# 07_DDR3.net
KiCad netlist of a schematic drawn in Altium Designer
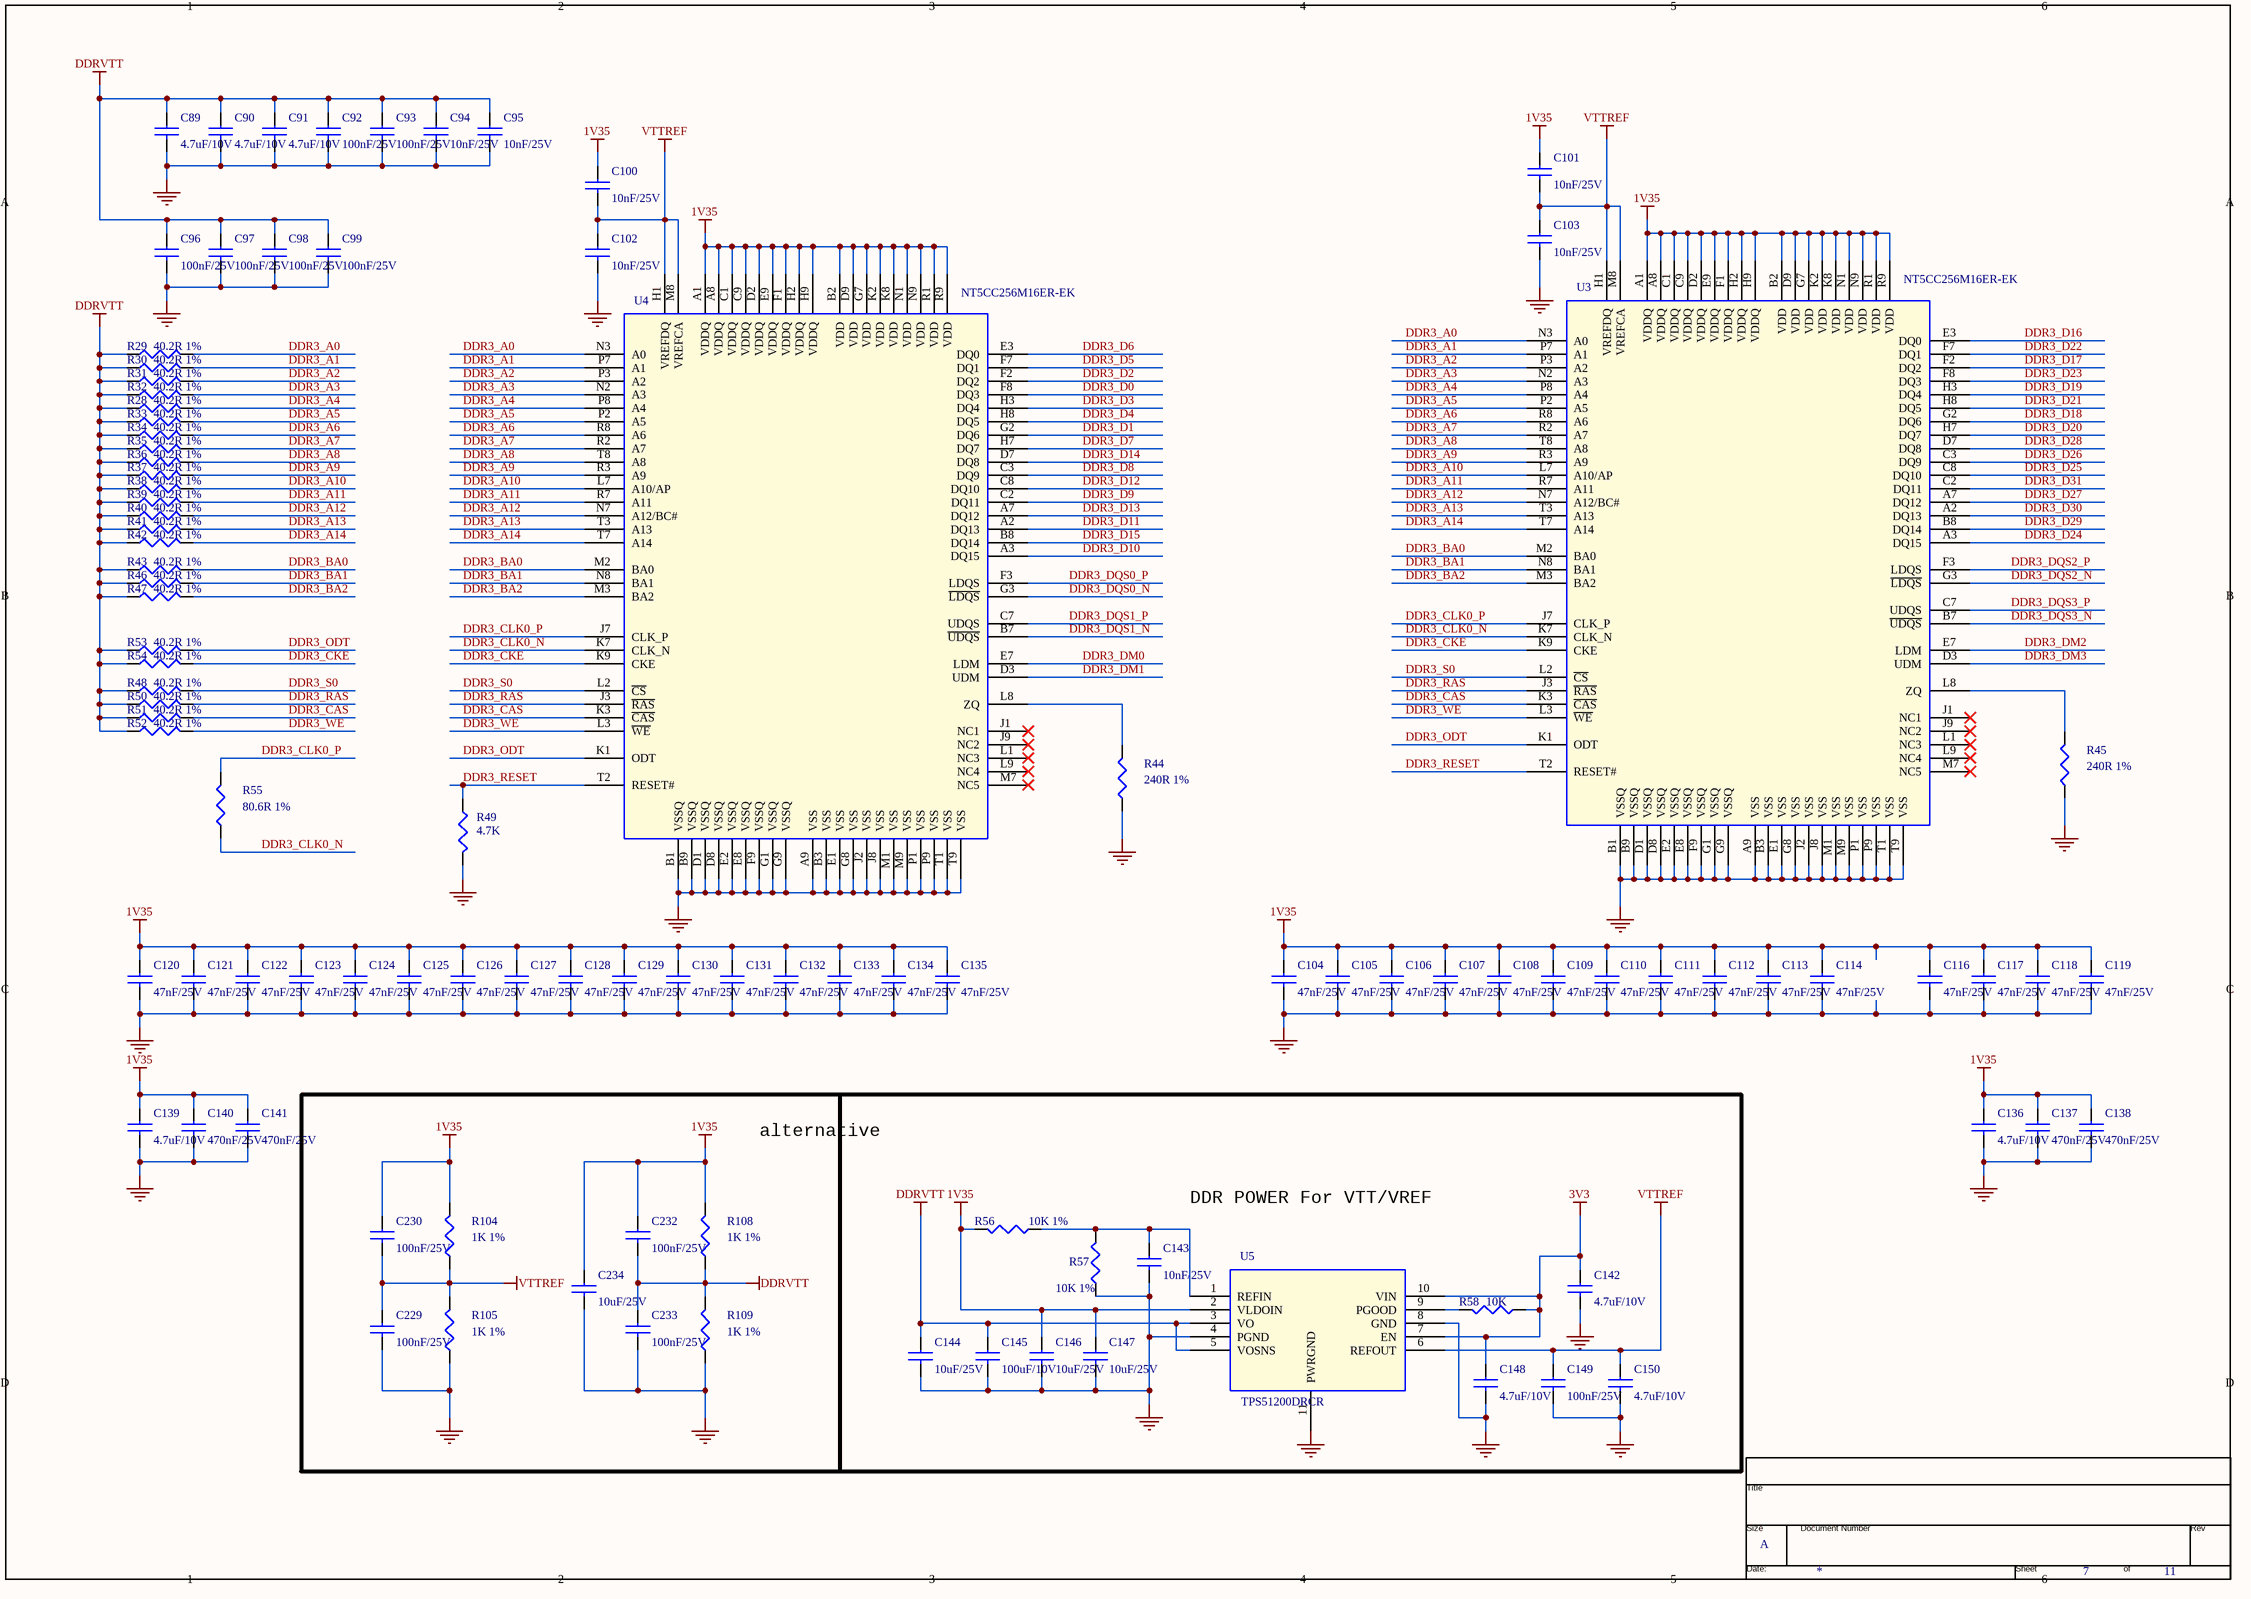
[diagram p0: 07_DDR3.SchDoc]

(export (version "E")
  (design (tool "Eeschema 10.0.6"))
  (components
    (comp (ref "C89") (value "4.7uF/10V") (footprint "C0402") (libsource (lib "*") (part "CAP NP_Dup1")))
    (comp (ref "C90") (value "4.7uF/10V") (footprint "C0402") (libsource (lib "*") (part "CAP NP_Dup1")))
    (comp (ref "C91") (value "4.7uF/10V") (footprint "C0402") (libsource (lib "*") (part "CAP NP_Dup1")))
    (comp (ref "C92") (value "100nF/25V") (footprint "C0402") (libsource (lib "*") (part "CAP NP_Dup1")))
    (comp (ref "C93") (value "100nF/25V") (footprint "C0402") (libsource (lib "*") (part "CAP NP_Dup1")))
    (comp (ref "C94") (value "10nF/25V") (footprint "C0402") (libsource (lib "*") (part "CAP NP_Dup1")))
    (comp (ref "C95") (value "10nF/25V") (footprint "C0402") (libsource (lib "*") (part "CAP NP_Dup1")))
    (comp (ref "C96") (value "100nF/25V") (footprint "C0402") (libsource (lib "*") (part "CAP NP_Dup1")))
    (comp (ref "C97") (value "100nF/25V") (footprint "C0402") (libsource (lib "*") (part "CAP NP_Dup1")))
    (comp (ref "C98") (value "100nF/25V") (footprint "C0402") (libsource (lib "*") (part "CAP NP_Dup1")))
    (comp (ref "C99") (value "100nF/25V") (footprint "C0402") (libsource (lib "*") (part "CAP NP_Dup1")))
    (comp (ref "C100") (value "10nF/25V") (footprint "C0402") (libsource (lib "*") (part "CAP NP_Dup1")))
    (comp (ref "C101") (value "10nF/25V") (footprint "C0402") (libsource (lib "*") (part "CAP NP_Dup1")))
    (comp (ref "C102") (value "10nF/25V") (footprint "C0402") (libsource (lib "*") (part "CAP NP_Dup1")))
    (comp (ref "C103") (value "10nF/25V") (footprint "C0402") (libsource (lib "*") (part "CAP NP_Dup1")))
    (comp (ref "C104") (value "47nF/25V") (footprint "C0402") (libsource (lib "*") (part "CAP NP_Dup1")))
    (comp (ref "C105") (value "47nF/25V") (footprint "C0402") (libsource (lib "*") (part "CAP NP_Dup1")))
    (comp (ref "C106") (value "47nF/25V") (footprint "C0402") (libsource (lib "*") (part "CAP NP_Dup1")))
    (comp (ref "C107") (value "47nF/25V") (footprint "C0402") (libsource (lib "*") (part "CAP NP_Dup1")))
    (comp (ref "C108") (value "47nF/25V") (footprint "C0402") (libsource (lib "*") (part "CAP NP_Dup1")))
    (comp (ref "C109") (value "47nF/25V") (footprint "C0402") (libsource (lib "*") (part "CAP NP_Dup1")))
    (comp (ref "C110") (value "47nF/25V") (footprint "C0402") (libsource (lib "*") (part "CAP NP_Dup1")))
    (comp (ref "C111") (value "47nF/25V") (footprint "C0402") (libsource (lib "*") (part "CAP NP_Dup1")))
    (comp (ref "C112") (value "47nF/25V") (footprint "C0402") (libsource (lib "*") (part "CAP NP_Dup1")))
    (comp (ref "C113") (value "47nF/25V") (footprint "C0402") (libsource (lib "*") (part "CAP NP_Dup1")))
    (comp (ref "C114") (value "47nF/25V") (footprint "C0402") (libsource (lib "*") (part "CAP NP_Dup1")))
    (comp (ref "C116") (value "47nF/25V") (footprint "C0402") (libsource (lib "*") (part "CAP NP_Dup1")))
    (comp (ref "C117") (value "47nF/25V") (footprint "C0402") (libsource (lib "*") (part "CAP NP_Dup1")))
    (comp (ref "C118") (value "47nF/25V") (footprint "C0402") (libsource (lib "*") (part "CAP NP_Dup1")))
    (comp (ref "C119") (value "47nF/25V") (footprint "C0402") (libsource (lib "*") (part "CAP NP_Dup1")))
    (comp (ref "C120") (value "47nF/25V") (footprint "C0402") (libsource (lib "*") (part "CAP NP_Dup1")))
    (comp (ref "C121") (value "47nF/25V") (footprint "C0402") (libsource (lib "*") (part "CAP NP_Dup1")))
    (comp (ref "C122") (value "47nF/25V") (footprint "C0402") (libsource (lib "*") (part "CAP NP_Dup1")))
    (comp (ref "C123") (value "47nF/25V") (footprint "C0402") (libsource (lib "*") (part "CAP NP_Dup1")))
    (comp (ref "C124") (value "47nF/25V") (footprint "C0402") (libsource (lib "*") (part "CAP NP_Dup1")))
    (comp (ref "C125") (value "47nF/25V") (footprint "C0402") (libsource (lib "*") (part "CAP NP_Dup1")))
    (comp (ref "C126") (value "47nF/25V") (footprint "C0402") (libsource (lib "*") (part "CAP NP_Dup1")))
    (comp (ref "C127") (value "47nF/25V") (footprint "C0402") (libsource (lib "*") (part "CAP NP_Dup1")))
    (comp (ref "C128") (value "47nF/25V") (footprint "C0402") (libsource (lib "*") (part "CAP NP_Dup1")))
    (comp (ref "C129") (value "47nF/25V") (footprint "C0402") (libsource (lib "*") (part "CAP NP_Dup1")))
    (comp (ref "C130") (value "47nF/25V") (footprint "C0402") (libsource (lib "*") (part "CAP NP_Dup1")))
    (comp (ref "C131") (value "47nF/25V") (footprint "C0402") (libsource (lib "*") (part "CAP NP_Dup1")))
    (comp (ref "C132") (value "47nF/25V") (footprint "C0402") (libsource (lib "*") (part "CAP NP_Dup1")))
    (comp (ref "C133") (value "47nF/25V") (footprint "C0402") (libsource (lib "*") (part "CAP NP_Dup1")))
    (comp (ref "C134") (value "47nF/25V") (footprint "C0402") (libsource (lib "*") (part "CAP NP_Dup1")))
    (comp (ref "C135") (value "47nF/25V") (footprint "C0402") (libsource (lib "*") (part "CAP NP_Dup1")))
    (comp (ref "C136") (value "4.7uF/10V") (footprint "C0402") (libsource (lib "*") (part "CAP NP_Dup1")))
    (comp (ref "C137") (value "470nF/25V") (footprint "C0402") (libsource (lib "*") (part "CAP NP_Dup1")))
    (comp (ref "C138") (value "470nF/25V") (footprint "C0402") (libsource (lib "*") (part "CAP NP_Dup1")))
    (comp (ref "C139") (value "4.7uF/10V") (footprint "C0402") (libsource (lib "*") (part "CAP NP_Dup1")))
    (comp (ref "C140") (value "470nF/25V") (footprint "C0402") (libsource (lib "*") (part "CAP NP_Dup1")))
    (comp (ref "C141") (value "470nF/25V") (footprint "C0402") (libsource (lib "*") (part "CAP NP_Dup1")))
    (comp (ref "C142") (value "4.7uF/10V") (footprint "C0402") (libsource (lib "*") (part "CAP NP_Dup1")))
    (comp (ref "C143") (value "10nF/25V") (footprint "C0402") (libsource (lib "*") (part "CAP NP_Dup1")))
    (comp (ref "C144") (value "10uF/25V") (footprint "C0603") (libsource (lib "*") (part "CAP NP_Dup1")))
    (comp (ref "C145") (value "100uF/10V") (footprint "1206C-N") (libsource (lib "*") (part "CAP NP_Dup1")))
    (comp (ref "C146") (value "10uF/25V") (footprint "C0603") (libsource (lib "*") (part "CAP NP_Dup1")))
    (comp (ref "C147") (value "10uF/25V") (footprint "C0603") (libsource (lib "*") (part "CAP NP_Dup1")))
    (comp (ref "C148") (value "4.7uF/10V") (footprint "C0402") (libsource (lib "*") (part "CAP NP_Dup1")))
    (comp (ref "C149") (value "100nF/25V") (footprint "C0402") (libsource (lib "*") (part "CAP NP_Dup1")))
    (comp (ref "C150") (value "4.7uF/10V") (footprint "C0402") (libsource (lib "*") (part "CAP NP_Dup1")))
    (comp (ref "C229") (value "100nF/25V") (footprint "C0402") (libsource (lib "*") (part "CAP NP_Dup1")))
    (comp (ref "C230") (value "100nF/25V") (footprint "C0402") (libsource (lib "*") (part "CAP NP_Dup1")))
    (comp (ref "C232") (value "100nF/25V") (footprint "C0402") (libsource (lib "*") (part "CAP NP_Dup1")))
    (comp (ref "C233") (value "100nF/25V") (footprint "C0402") (libsource (lib "*") (part "CAP NP_Dup1")))
    (comp (ref "C234") (value "10uF/25V") (footprint "C0603") (libsource (lib "*") (part "CAP NP_Dup1")))
    (comp (ref "R28") (value "40.2R 1%") (footprint "R0402") (libsource (lib "*") (part "RESISTOR_Dup1")))
    (comp (ref "R29") (value "40.2R 1%") (footprint "R0402") (libsource (lib "*") (part "RESISTOR_Dup1")))
    (comp (ref "R30") (value "40.2R 1%") (footprint "R0402") (libsource (lib "*") (part "RESISTOR_Dup1")))
    (comp (ref "R31") (value "40.2R 1%") (footprint "R0402") (libsource (lib "*") (part "RESISTOR_Dup1")))
    (comp (ref "R32") (value "40.2R 1%") (footprint "R0402") (libsource (lib "*") (part "RESISTOR_Dup1")))
    (comp (ref "R33") (value "40.2R 1%") (footprint "R0402") (libsource (lib "*") (part "RESISTOR_Dup1")))
    (comp (ref "R34") (value "40.2R 1%") (footprint "R0402") (libsource (lib "*") (part "RESISTOR_Dup1")))
    (comp (ref "R35") (value "40.2R 1%") (footprint "R0402") (libsource (lib "*") (part "RESISTOR_Dup1")))
    (comp (ref "R36") (value "40.2R 1%") (footprint "R0402") (libsource (lib "*") (part "RESISTOR_Dup1")))
    (comp (ref "R37") (value "40.2R 1%") (footprint "R0402") (libsource (lib "*") (part "RESISTOR_Dup1")))
    (comp (ref "R38") (value "40.2R 1%") (footprint "R0402") (libsource (lib "*") (part "RESISTOR_Dup1")))
    (comp (ref "R39") (value "40.2R 1%") (footprint "R0402") (libsource (lib "*") (part "RESISTOR_Dup1")))
    (comp (ref "R40") (value "40.2R 1%") (footprint "R0402") (libsource (lib "*") (part "RESISTOR_Dup1")))
    (comp (ref "R41") (value "40.2R 1%") (footprint "R0402") (libsource (lib "*") (part "RESISTOR_Dup1")))
    (comp (ref "R42") (value "40.2R 1%") (footprint "R0402") (libsource (lib "*") (part "RESISTOR_Dup1")))
    (comp (ref "R43") (value "40.2R 1%") (footprint "R0402") (libsource (lib "*") (part "RESISTOR_Dup1")))
    (comp (ref "R44") (value "240R 1%") (footprint "R0402") (libsource (lib "*") (part "RESISTOR_Dup1")))
    (comp (ref "R45") (value "240R 1%") (footprint "R0402") (libsource (lib "*") (part "RESISTOR_Dup1")))
    (comp (ref "R46") (value "40.2R 1%") (footprint "R0402") (libsource (lib "*") (part "RESISTOR_Dup1")))
    (comp (ref "R47") (value "40.2R 1%") (footprint "R0402") (libsource (lib "*") (part "RESISTOR_Dup1")))
    (comp (ref "R48") (value "40.2R 1%") (footprint "R0402") (libsource (lib "*") (part "RESISTOR_Dup1")))
    (comp (ref "R49") (value "4.7K") (footprint "R0402") (libsource (lib "*") (part "RESISTOR_Dup1")))
    (comp (ref "R50") (value "40.2R 1%") (footprint "R0402") (libsource (lib "*") (part "RESISTOR_Dup1")))
    (comp (ref "R51") (value "40.2R 1%") (footprint "R0402") (libsource (lib "*") (part "RESISTOR_Dup1")))
    (comp (ref "R52") (value "40.2R 1%") (footprint "R0402") (libsource (lib "*") (part "RESISTOR_Dup1")))
    (comp (ref "R53") (value "40.2R 1%") (footprint "R0402") (libsource (lib "*") (part "RESISTOR_Dup1")))
    (comp (ref "R54") (value "40.2R 1%") (footprint "R0402") (libsource (lib "*") (part "RESISTOR_Dup1")))
    (comp (ref "R55") (value "80.6R 1%") (footprint "R0402") (libsource (lib "*") (part "RESISTOR_Dup1")))
    (comp (ref "R56") (value "10K 1%") (footprint "R0402") (libsource (lib "*") (part "RESISTOR_Dup1")))
    (comp (ref "R57") (value "10K 1%") (footprint "R0402") (libsource (lib "*") (part "RESISTOR_Dup1")))
    (comp (ref "R58") (value "10K") (footprint "R0402") (libsource (lib "*") (part "RESISTOR_Dup1")))
    (comp (ref "R104") (value "1K 1%") (footprint "R0402") (libsource (lib "*") (part "RESISTOR_Dup1")))
    (comp (ref "R105") (value "1K 1%") (footprint "R0402") (libsource (lib "*") (part "RESISTOR_Dup1")))
    (comp (ref "R108")
      (value "1K 1%")
      (footprint "R0603")
      (description "0603")
      (libsource (lib "*") (part "RESISTOR_Dup1"))
    )
    (comp (ref "R109")
      (value "1K 1%")
      (footprint "R0603")
      (description "0603")
      (libsource (lib "*") (part "RESISTOR_Dup1"))
    )
    (comp (ref "U3")
      (value "NT5CC256M16ER-EK")
      (footprint "FBGA_96")
      (libsource (lib "*") (part "H5TQ4G63AFR-PBI"))
    )
    (comp (ref "U4")
      (value "NT5CC256M16ER-EK")
      (footprint "FBGA_96")
      (libsource (lib "*") (part "H5TQ4G63AFR-PBI"))
    )
    (comp (ref "U5")
      (value "TPS51200DRCR")
      (footprint "TPS_QFN10")
      (libsource (lib "*") (part "TPS51200DRCR"))
    )
  )
  (nets
    (net (code "1") (name "/DDR3_A0") (class "Default")
      (node (ref "R29") (pin "2") (pinfunction "2_2") (pintype "passive"))
      (node (ref "U3") (pin "N3") (pinfunction "A0_N3") (pintype "passive"))
      (node (ref "U4") (pin "N3") (pinfunction "A0_N3") (pintype "passive"))
    )
    (net (code "2") (name "/DDR3_A1") (class "Default")
      (node (ref "R30") (pin "2") (pinfunction "2_2") (pintype "passive"))
      (node (ref "U3") (pin "P7") (pinfunction "A1_P7") (pintype "passive"))
      (node (ref "U4") (pin "P7") (pinfunction "A1_P7") (pintype "passive"))
    )
    (net (code "3") (name "/DDR3_A2") (class "Default")
      (node (ref "R31") (pin "2") (pinfunction "2_2") (pintype "passive"))
      (node (ref "U3") (pin "P3") (pinfunction "A2_P3") (pintype "passive"))
      (node (ref "U4") (pin "P3") (pinfunction "A2_P3") (pintype "passive"))
    )
    (net (code "4") (name "/DDR3_A3") (class "Default")
      (node (ref "R32") (pin "2") (pinfunction "2_2") (pintype "passive"))
      (node (ref "U3") (pin "N2") (pinfunction "A3_N2") (pintype "passive"))
      (node (ref "U4") (pin "N2") (pinfunction "A3_N2") (pintype "passive"))
    )
    (net (code "5") (name "/DDR3_A4") (class "Default")
      (node (ref "R28") (pin "2") (pinfunction "2_2") (pintype "passive"))
      (node (ref "U3") (pin "P8") (pinfunction "A4_P8") (pintype "passive"))
      (node (ref "U4") (pin "P8") (pinfunction "A4_P8") (pintype "passive"))
    )
    (net (code "6") (name "/DDR3_A5") (class "Default")
      (node (ref "R33") (pin "2") (pinfunction "2_2") (pintype "passive"))
      (node (ref "U3") (pin "P2") (pinfunction "A5_P2") (pintype "passive"))
      (node (ref "U4") (pin "P2") (pinfunction "A5_P2") (pintype "passive"))
    )
    (net (code "7") (name "/DDR3_A6") (class "Default")
      (node (ref "R34") (pin "2") (pinfunction "2_2") (pintype "passive"))
      (node (ref "U3") (pin "R8") (pinfunction "A6_R8") (pintype "passive"))
      (node (ref "U4") (pin "R8") (pinfunction "A6_R8") (pintype "passive"))
    )
    (net (code "8") (name "/DDR3_A7") (class "Default")
      (node (ref "R35") (pin "2") (pinfunction "2_2") (pintype "passive"))
      (node (ref "U3") (pin "R2") (pinfunction "A7_R2") (pintype "passive"))
      (node (ref "U4") (pin "R2") (pinfunction "A7_R2") (pintype "passive"))
    )
    (net (code "9") (name "/DDR3_A8") (class "Default")
      (node (ref "R36") (pin "2") (pinfunction "2_2") (pintype "passive"))
      (node (ref "U3") (pin "T8") (pinfunction "A8_T8") (pintype "passive"))
      (node (ref "U4") (pin "T8") (pinfunction "A8_T8") (pintype "passive"))
    )
    (net (code "10") (name "/DDR3_A9") (class "Default")
      (node (ref "R37") (pin "2") (pinfunction "2_2") (pintype "passive"))
      (node (ref "U3") (pin "R3") (pinfunction "A9_R3") (pintype "passive"))
      (node (ref "U4") (pin "R3") (pinfunction "A9_R3") (pintype "passive"))
    )
    (net (code "11") (name "/DDR3_A10") (class "Default")
      (node (ref "R38") (pin "2") (pinfunction "2_2") (pintype "passive"))
      (node (ref "U3") (pin "L7") (pinfunction "A10/AP_L7") (pintype "passive"))
      (node (ref "U4") (pin "L7") (pinfunction "A10/AP_L7") (pintype "passive"))
    )
    (net (code "12") (name "/DDR3_A11") (class "Default")
      (node (ref "R39") (pin "2") (pinfunction "2_2") (pintype "passive"))
      (node (ref "U3") (pin "R7") (pinfunction "A11_R7") (pintype "passive"))
      (node (ref "U4") (pin "R7") (pinfunction "A11_R7") (pintype "passive"))
    )
    (net (code "13") (name "/DDR3_A12") (class "Default")
      (node (ref "R40") (pin "2") (pinfunction "2_2") (pintype "passive"))
      (node (ref "U3") (pin "N7") (pinfunction "A12/BC#_N7") (pintype "passive"))
      (node (ref "U4") (pin "N7") (pinfunction "A12/BC#_N7") (pintype "passive"))
    )
    (net (code "14") (name "/DDR3_A13") (class "Default")
      (node (ref "R41") (pin "2") (pinfunction "2_2") (pintype "passive"))
      (node (ref "U3") (pin "T3") (pinfunction "A13_T3") (pintype "passive"))
      (node (ref "U4") (pin "T3") (pinfunction "A13_T3") (pintype "passive"))
    )
    (net (code "15") (name "/DDR3_A14") (class "Default")
      (node (ref "R42") (pin "2") (pinfunction "2_2") (pintype "passive"))
      (node (ref "U3") (pin "T7") (pinfunction "A14_T7") (pintype "power_in"))
      (node (ref "U4") (pin "T7") (pinfunction "A14_T7") (pintype "power_in"))
    )
    (net (code "16") (name "/DDR3_BA0") (class "Default")
      (node (ref "R43") (pin "2") (pinfunction "2_2") (pintype "passive"))
      (node (ref "U3") (pin "M2") (pinfunction "BA0_M2") (pintype "passive"))
      (node (ref "U4") (pin "M2") (pinfunction "BA0_M2") (pintype "passive"))
    )
    (net (code "17") (name "/DDR3_BA1") (class "Default")
      (node (ref "R46") (pin "2") (pinfunction "2_2") (pintype "passive"))
      (node (ref "U3") (pin "N8") (pinfunction "BA1_N8") (pintype "passive"))
      (node (ref "U4") (pin "N8") (pinfunction "BA1_N8") (pintype "passive"))
    )
    (net (code "18") (name "/DDR3_BA2") (class "Default")
      (node (ref "R47") (pin "2") (pinfunction "2_2") (pintype "passive"))
      (node (ref "U3") (pin "M3") (pinfunction "BA2_M3") (pintype "passive"))
      (node (ref "U4") (pin "M3") (pinfunction "BA2_M3") (pintype "passive"))
    )
    (net (code "19") (name "/DDR3_CAS") (class "Default")
      (node (ref "R51") (pin "2") (pinfunction "2_2") (pintype "passive"))
      (node (ref "U3") (pin "K3") (pinfunction "~{CAS}_K3") (pintype "passive"))
      (node (ref "U4") (pin "K3") (pinfunction "~{CAS}_K3") (pintype "passive"))
    )
    (net (code "20") (name "/DDR3_CKE") (class "Default")
      (node (ref "R54") (pin "2") (pinfunction "2_2") (pintype "passive"))
      (node (ref "U3") (pin "K9") (pinfunction "CKE_K9") (pintype "passive"))
      (node (ref "U4") (pin "K9") (pinfunction "CKE_K9") (pintype "passive"))
    )
    (net (code "21") (name "/DDR3_CLK0_N") (class "Default")
      (node (ref "R55") (pin "1") (pinfunction "1_1") (pintype "passive"))
      (node (ref "U3") (pin "K7") (pinfunction "CLK_N_K7") (pintype "passive"))
      (node (ref "U4") (pin "K7") (pinfunction "CLK_N_K7") (pintype "passive"))
    )
    (net (code "22") (name "/DDR3_CLK0_P") (class "Default")
      (node (ref "R55") (pin "2") (pinfunction "2_2") (pintype "passive"))
      (node (ref "U3") (pin "J7") (pinfunction "CLK_P_J7") (pintype "passive"))
      (node (ref "U4") (pin "J7") (pinfunction "CLK_P_J7") (pintype "passive"))
    )
    (net (code "23") (name "/DDR3_D0") (class "Default")
      (node (ref "U4") (pin "F8") (pinfunction "DQ3_F8") (pintype "power_in"))
    )
    (net (code "24") (name "/DDR3_D1") (class "Default")
      (node (ref "U4") (pin "G2") (pinfunction "DQ6_G2") (pintype "power_in"))
    )
    (net (code "25") (name "/DDR3_D2") (class "Default")
      (node (ref "U4") (pin "F2") (pinfunction "DQ2_F2") (pintype "power_in"))
    )
    (net (code "26") (name "/DDR3_D3") (class "Default")
      (node (ref "U4") (pin "H3") (pinfunction "DQ4_H3") (pintype "power_in"))
    )
    (net (code "27") (name "/DDR3_D4") (class "Default")
      (node (ref "U4") (pin "H8") (pinfunction "DQ5_H8") (pintype "power_in"))
    )
    (net (code "28") (name "/DDR3_D5") (class "Default")
      (node (ref "U4") (pin "F7") (pinfunction "DQ1_F7") (pintype "power_in"))
    )
    (net (code "29") (name "/DDR3_D6") (class "Default")
      (node (ref "U4") (pin "E3") (pinfunction "DQ0_E3") (pintype "power_in"))
    )
    (net (code "30") (name "/DDR3_D7") (class "Default")
      (node (ref "U4") (pin "H7") (pinfunction "DQ7_H7") (pintype "power_in"))
    )
    (net (code "31") (name "/DDR3_D8") (class "Default")
      (node (ref "U4") (pin "C3") (pinfunction "DQ9_C3") (pintype "power_in"))
    )
    (net (code "32") (name "/DDR3_D9") (class "Default")
      (node (ref "U4") (pin "C2") (pinfunction "DQ11_C2") (pintype "power_in"))
    )
    (net (code "33") (name "/DDR3_D10") (class "Default")
      (node (ref "U4") (pin "A3") (pinfunction "DQ15_A3") (pintype "power_in"))
    )
    (net (code "34") (name "/DDR3_D11") (class "Default")
      (node (ref "U4") (pin "A2") (pinfunction "DQ13_A2") (pintype "power_in"))
    )
    (net (code "35") (name "/DDR3_D12") (class "Default")
      (node (ref "U4") (pin "C8") (pinfunction "DQ10_C8") (pintype "power_in"))
    )
    (net (code "36") (name "/DDR3_D13") (class "Default")
      (node (ref "U4") (pin "A7") (pinfunction "DQ12_A7") (pintype "power_in"))
    )
    (net (code "37") (name "/DDR3_D14") (class "Default")
      (node (ref "U4") (pin "D7") (pinfunction "DQ8_D7") (pintype "power_in"))
    )
    (net (code "38") (name "/DDR3_D15") (class "Default")
      (node (ref "U4") (pin "B8") (pinfunction "DQ14_B8") (pintype "power_in"))
    )
    (net (code "39") (name "/DDR3_D16") (class "Default")
      (node (ref "U3") (pin "E3") (pinfunction "DQ0_E3") (pintype "power_in"))
    )
    (net (code "40") (name "/DDR3_D17") (class "Default")
      (node (ref "U3") (pin "F2") (pinfunction "DQ2_F2") (pintype "power_in"))
    )
    (net (code "41") (name "/DDR3_D18") (class "Default")
      (node (ref "U3") (pin "G2") (pinfunction "DQ6_G2") (pintype "power_in"))
    )
    (net (code "42") (name "/DDR3_D19") (class "Default")
      (node (ref "U3") (pin "H3") (pinfunction "DQ4_H3") (pintype "power_in"))
    )
    (net (code "43") (name "/DDR3_D20") (class "Default")
      (node (ref "U3") (pin "H7") (pinfunction "DQ7_H7") (pintype "power_in"))
    )
    (net (code "44") (name "/DDR3_D21") (class "Default")
      (node (ref "U3") (pin "H8") (pinfunction "DQ5_H8") (pintype "power_in"))
    )
    (net (code "45") (name "/DDR3_D22") (class "Default")
      (node (ref "U3") (pin "F7") (pinfunction "DQ1_F7") (pintype "power_in"))
    )
    (net (code "46") (name "/DDR3_D23") (class "Default")
      (node (ref "U3") (pin "F8") (pinfunction "DQ3_F8") (pintype "power_in"))
    )
    (net (code "47") (name "/DDR3_D24") (class "Default")
      (node (ref "U3") (pin "A3") (pinfunction "DQ15_A3") (pintype "power_in"))
    )
    (net (code "48") (name "/DDR3_D25") (class "Default")
      (node (ref "U3") (pin "C8") (pinfunction "DQ10_C8") (pintype "power_in"))
    )
    (net (code "49") (name "/DDR3_D26") (class "Default")
      (node (ref "U3") (pin "C3") (pinfunction "DQ9_C3") (pintype "power_in"))
    )
    (net (code "50") (name "/DDR3_D27") (class "Default")
      (node (ref "U3") (pin "A7") (pinfunction "DQ12_A7") (pintype "power_in"))
    )
    (net (code "51") (name "/DDR3_D28") (class "Default")
      (node (ref "U3") (pin "D7") (pinfunction "DQ8_D7") (pintype "power_in"))
    )
    (net (code "52") (name "/DDR3_D29") (class "Default")
      (node (ref "U3") (pin "B8") (pinfunction "DQ14_B8") (pintype "power_in"))
    )
    (net (code "53") (name "/DDR3_D30") (class "Default")
      (node (ref "U3") (pin "A2") (pinfunction "DQ13_A2") (pintype "power_in"))
    )
    (net (code "54") (name "/DDR3_D31") (class "Default")
      (node (ref "U3") (pin "C2") (pinfunction "DQ11_C2") (pintype "power_in"))
    )
    (net (code "55") (name "/DDR3_DM0") (class "Default")
      (node (ref "U4") (pin "E7") (pinfunction "LDM_E7") (pintype "passive"))
    )
    (net (code "56") (name "/DDR3_DM1") (class "Default")
      (node (ref "U4") (pin "D3") (pinfunction "UDM_D3") (pintype "passive"))
    )
    (net (code "57") (name "/DDR3_DM2") (class "Default")
      (node (ref "U3") (pin "E7") (pinfunction "LDM_E7") (pintype "passive"))
    )
    (net (code "58") (name "/DDR3_DM3") (class "Default")
      (node (ref "U3") (pin "D3") (pinfunction "UDM_D3") (pintype "passive"))
    )
    (net (code "59") (name "/DDR3_DQS0_N") (class "Default")
      (node (ref "U4") (pin "G3") (pinfunction "~{LDQS}_G3") (pintype "power_in"))
    )
    (net (code "60") (name "/DDR3_DQS0_P") (class "Default")
      (node (ref "U4") (pin "F3") (pinfunction "LDQS_F3") (pintype "power_in"))
    )
    (net (code "61") (name "/DDR3_DQS1_N") (class "Default")
      (node (ref "U4") (pin "B7") (pinfunction "~{UDQS}_B7") (pintype "power_in"))
    )
    (net (code "62") (name "/DDR3_DQS1_P") (class "Default")
      (node (ref "U4") (pin "C7") (pinfunction "UDQS_C7") (pintype "power_in"))
    )
    (net (code "63") (name "/DDR3_DQS2_N") (class "Default")
      (node (ref "U3") (pin "G3") (pinfunction "~{LDQS}_G3") (pintype "power_in"))
    )
    (net (code "64") (name "/DDR3_DQS2_P") (class "Default")
      (node (ref "U3") (pin "F3") (pinfunction "LDQS_F3") (pintype "power_in"))
    )
    (net (code "65") (name "/DDR3_DQS3_N") (class "Default")
      (node (ref "U3") (pin "B7") (pinfunction "~{UDQS}_B7") (pintype "power_in"))
    )
    (net (code "66") (name "/DDR3_DQS3_P") (class "Default")
      (node (ref "U3") (pin "C7") (pinfunction "UDQS_C7") (pintype "power_in"))
    )
    (net (code "67") (name "/DDR3_ODT") (class "Default")
      (node (ref "R53") (pin "2") (pinfunction "2_2") (pintype "passive"))
      (node (ref "U3") (pin "K1") (pinfunction "ODT_K1") (pintype "passive"))
      (node (ref "U4") (pin "K1") (pinfunction "ODT_K1") (pintype "passive"))
    )
    (net (code "68") (name "/DDR3_RAS") (class "Default")
      (node (ref "R50") (pin "2") (pinfunction "2_2") (pintype "passive"))
      (node (ref "U3") (pin "J3") (pinfunction "~{RAS}_J3") (pintype "passive"))
      (node (ref "U4") (pin "J3") (pinfunction "~{RAS}_J3") (pintype "passive"))
    )
    (net (code "69") (name "/DDR3_RESET") (class "Default")
      (node (ref "R49") (pin "1") (pinfunction "1_1") (pintype "passive"))
      (node (ref "U3") (pin "T2") (pinfunction "RESET#_T2") (pintype "power_in"))
      (node (ref "U4") (pin "T2") (pinfunction "RESET#_T2") (pintype "power_in"))
    )
    (net (code "70") (name "/DDR3_S0") (class "Default")
      (node (ref "R48") (pin "2") (pinfunction "2_2") (pintype "passive"))
      (node (ref "U3") (pin "L2") (pinfunction "~{CS}_L2") (pintype "passive"))
      (node (ref "U4") (pin "L2") (pinfunction "~{CS}_L2") (pintype "passive"))
    )
    (net (code "71") (name "/DDR3_WE") (class "Default")
      (node (ref "R52") (pin "2") (pinfunction "2_2") (pintype "passive"))
      (node (ref "U3") (pin "L3") (pinfunction "~{WE}_L3") (pintype "passive"))
      (node (ref "U4") (pin "L3") (pinfunction "~{WE}_L3") (pintype "passive"))
    )
    (net (code "72") (name "1V35") (class "Default")
      (node (ref "C100") (pin "1") (pinfunction "1_1") (pintype "passive"))
      (node (ref "C101") (pin "1") (pinfunction "1_1") (pintype "passive"))
      (node (ref "C104") (pin "1") (pinfunction "1_1") (pintype "passive"))
      (node (ref "C105") (pin "1") (pinfunction "1_1") (pintype "passive"))
      (node (ref "C106") (pin "1") (pinfunction "1_1") (pintype "passive"))
      (node (ref "C107") (pin "1") (pinfunction "1_1") (pintype "passive"))
      (node (ref "C108") (pin "1") (pinfunction "1_1") (pintype "passive"))
      (node (ref "C109") (pin "1") (pinfunction "1_1") (pintype "passive"))
      (node (ref "C110") (pin "1") (pinfunction "1_1") (pintype "passive"))
      (node (ref "C111") (pin "1") (pinfunction "1_1") (pintype "passive"))
      (node (ref "C112") (pin "1") (pinfunction "1_1") (pintype "passive"))
      (node (ref "C113") (pin "1") (pinfunction "1_1") (pintype "passive"))
      (node (ref "C114") (pin "1") (pinfunction "1_1") (pintype "passive"))
      (node (ref "C116") (pin "1") (pinfunction "1_1") (pintype "passive"))
      (node (ref "C117") (pin "1") (pinfunction "1_1") (pintype "passive"))
      (node (ref "C118") (pin "1") (pinfunction "1_1") (pintype "passive"))
      (node (ref "C119") (pin "1") (pinfunction "1_1") (pintype "passive"))
      (node (ref "C120") (pin "1") (pinfunction "1_1") (pintype "passive"))
      (node (ref "C121") (pin "1") (pinfunction "1_1") (pintype "passive"))
      (node (ref "C122") (pin "1") (pinfunction "1_1") (pintype "passive"))
      (node (ref "C123") (pin "1") (pinfunction "1_1") (pintype "passive"))
      (node (ref "C124") (pin "1") (pinfunction "1_1") (pintype "passive"))
      (node (ref "C125") (pin "1") (pinfunction "1_1") (pintype "passive"))
      (node (ref "C126") (pin "1") (pinfunction "1_1") (pintype "passive"))
      (node (ref "C127") (pin "1") (pinfunction "1_1") (pintype "passive"))
      (node (ref "C128") (pin "1") (pinfunction "1_1") (pintype "passive"))
      (node (ref "C129") (pin "1") (pinfunction "1_1") (pintype "passive"))
      (node (ref "C130") (pin "1") (pinfunction "1_1") (pintype "passive"))
      (node (ref "C131") (pin "1") (pinfunction "1_1") (pintype "passive"))
      (node (ref "C132") (pin "1") (pinfunction "1_1") (pintype "passive"))
      (node (ref "C133") (pin "1") (pinfunction "1_1") (pintype "passive"))
      (node (ref "C134") (pin "1") (pinfunction "1_1") (pintype "passive"))
      (node (ref "C135") (pin "1") (pinfunction "1_1") (pintype "passive"))
      (node (ref "C136") (pin "1") (pinfunction "1_1") (pintype "passive"))
      (node (ref "C137") (pin "1") (pinfunction "1_1") (pintype "passive"))
      (node (ref "C138") (pin "1") (pinfunction "1_1") (pintype "passive"))
      (node (ref "C139") (pin "1") (pinfunction "1_1") (pintype "passive"))
      (node (ref "C140") (pin "1") (pinfunction "1_1") (pintype "passive"))
      (node (ref "C141") (pin "1") (pinfunction "1_1") (pintype "passive"))
      (node (ref "C146") (pin "1") (pinfunction "1_1") (pintype "passive"))
      (node (ref "C147") (pin "1") (pinfunction "1_1") (pintype "passive"))
      (node (ref "C230") (pin "1") (pinfunction "1_1") (pintype "passive"))
      (node (ref "C232") (pin "1") (pinfunction "1_1") (pintype "passive"))
      (node (ref "C234") (pin "1") (pinfunction "1_1") (pintype "passive"))
      (node (ref "R104") (pin "2") (pinfunction "2_2") (pintype "passive"))
      (node (ref "R108") (pin "2") (pinfunction "2_2") (pintype "passive"))
      (node (ref "R56") (pin "2") (pinfunction "2_2") (pintype "passive"))
      (node (ref "U3") (pin "A1") (pinfunction "VDDQ_A1") (pintype "power_in"))
      (node (ref "U3") (pin "A8") (pinfunction "VDDQ_A8") (pintype "power_in"))
      (node (ref "U3") (pin "B2") (pinfunction "VDD_B2") (pintype "power_in"))
      (node (ref "U3") (pin "C1") (pinfunction "VDDQ_C1") (pintype "power_in"))
      (node (ref "U3") (pin "C9") (pinfunction "VDDQ_C9") (pintype "power_in"))
      (node (ref "U3") (pin "D2") (pinfunction "VDDQ_D2") (pintype "power_in"))
      (node (ref "U3") (pin "D9") (pinfunction "VDD_D9") (pintype "power_in"))
      (node (ref "U3") (pin "E9") (pinfunction "VDDQ_E9") (pintype "power_in"))
      (node (ref "U3") (pin "F1") (pinfunction "VDDQ_F1") (pintype "power_in"))
      (node (ref "U3") (pin "G7") (pinfunction "VDD_G7") (pintype "power_in"))
      (node (ref "U3") (pin "H2") (pinfunction "VDDQ_H2") (pintype "power_in"))
      (node (ref "U3") (pin "H9") (pinfunction "VDDQ_H9") (pintype "power_in"))
      (node (ref "U3") (pin "K2") (pinfunction "VDD_K2") (pintype "power_in"))
      (node (ref "U3") (pin "K8") (pinfunction "VDD_K8") (pintype "power_in"))
      (node (ref "U3") (pin "N1") (pinfunction "VDD_N1") (pintype "power_in"))
      (node (ref "U3") (pin "N9") (pinfunction "VDD_N9") (pintype "power_in"))
      (node (ref "U3") (pin "R1") (pinfunction "VDD_R1") (pintype "power_in"))
      (node (ref "U3") (pin "R9") (pinfunction "VDD_R9") (pintype "power_in"))
      (node (ref "U4") (pin "A1") (pinfunction "VDDQ_A1") (pintype "power_in"))
      (node (ref "U4") (pin "A8") (pinfunction "VDDQ_A8") (pintype "power_in"))
      (node (ref "U4") (pin "B2") (pinfunction "VDD_B2") (pintype "power_in"))
      (node (ref "U4") (pin "C1") (pinfunction "VDDQ_C1") (pintype "power_in"))
      (node (ref "U4") (pin "C9") (pinfunction "VDDQ_C9") (pintype "power_in"))
      (node (ref "U4") (pin "D2") (pinfunction "VDDQ_D2") (pintype "power_in"))
      (node (ref "U4") (pin "D9") (pinfunction "VDD_D9") (pintype "power_in"))
      (node (ref "U4") (pin "E9") (pinfunction "VDDQ_E9") (pintype "power_in"))
      (node (ref "U4") (pin "F1") (pinfunction "VDDQ_F1") (pintype "power_in"))
      (node (ref "U4") (pin "G7") (pinfunction "VDD_G7") (pintype "power_in"))
      (node (ref "U4") (pin "H2") (pinfunction "VDDQ_H2") (pintype "power_in"))
      (node (ref "U4") (pin "H9") (pinfunction "VDDQ_H9") (pintype "power_in"))
      (node (ref "U4") (pin "K2") (pinfunction "VDD_K2") (pintype "power_in"))
      (node (ref "U4") (pin "K8") (pinfunction "VDD_K8") (pintype "power_in"))
      (node (ref "U4") (pin "N1") (pinfunction "VDD_N1") (pintype "power_in"))
      (node (ref "U4") (pin "N9") (pinfunction "VDD_N9") (pintype "power_in"))
      (node (ref "U4") (pin "R1") (pinfunction "VDD_R1") (pintype "power_in"))
      (node (ref "U4") (pin "R9") (pinfunction "VDD_R9") (pintype "power_in"))
      (node (ref "U5") (pin "2") (pinfunction "VLDOIN_2") (pintype "passive"))
    )
    (net (code "73") (name "3V3") (class "Default")
      (node (ref "C142") (pin "1") (pinfunction "1_1") (pintype "passive"))
      (node (ref "C148") (pin "1") (pinfunction "1_1") (pintype "passive"))
      (node (ref "R58") (pin "1") (pinfunction "1_1") (pintype "passive"))
      (node (ref "U5") (pin "10") (pinfunction "VIN_10") (pintype "passive"))
      (node (ref "U5") (pin "7") (pinfunction "EN_7") (pintype "passive"))
    )
    (net (code "74") (name "DDRVTT") (class "Default")
      (node (ref "C144") (pin "1") (pinfunction "1_1") (pintype "passive"))
      (node (ref "C145") (pin "1") (pinfunction "1_1") (pintype "passive"))
      (node (ref "C232") (pin "2") (pinfunction "2_2") (pintype "passive"))
      (node (ref "C233") (pin "1") (pinfunction "1_1") (pintype "passive"))
      (node (ref "C89") (pin "1") (pinfunction "1_1") (pintype "passive"))
      (node (ref "C90") (pin "1") (pinfunction "1_1") (pintype "passive"))
      (node (ref "C91") (pin "1") (pinfunction "1_1") (pintype "passive"))
      (node (ref "C92") (pin "1") (pinfunction "1_1") (pintype "passive"))
      (node (ref "C93") (pin "1") (pinfunction "1_1") (pintype "passive"))
      (node (ref "C94") (pin "1") (pinfunction "1_1") (pintype "passive"))
      (node (ref "C95") (pin "1") (pinfunction "1_1") (pintype "passive"))
      (node (ref "C96") (pin "1") (pinfunction "1_1") (pintype "passive"))
      (node (ref "C97") (pin "1") (pinfunction "1_1") (pintype "passive"))
      (node (ref "C98") (pin "1") (pinfunction "1_1") (pintype "passive"))
      (node (ref "C99") (pin "1") (pinfunction "1_1") (pintype "passive"))
      (node (ref "R108") (pin "1") (pinfunction "1_1") (pintype "passive"))
      (node (ref "R109") (pin "2") (pinfunction "2_2") (pintype "passive"))
      (node (ref "R28") (pin "1") (pinfunction "1_1") (pintype "passive"))
      (node (ref "R29") (pin "1") (pinfunction "1_1") (pintype "passive"))
      (node (ref "R30") (pin "1") (pinfunction "1_1") (pintype "passive"))
      (node (ref "R31") (pin "1") (pinfunction "1_1") (pintype "passive"))
      (node (ref "R32") (pin "1") (pinfunction "1_1") (pintype "passive"))
      (node (ref "R33") (pin "1") (pinfunction "1_1") (pintype "passive"))
      (node (ref "R34") (pin "1") (pinfunction "1_1") (pintype "passive"))
      (node (ref "R35") (pin "1") (pinfunction "1_1") (pintype "passive"))
      (node (ref "R36") (pin "1") (pinfunction "1_1") (pintype "passive"))
      (node (ref "R37") (pin "1") (pinfunction "1_1") (pintype "passive"))
      (node (ref "R38") (pin "1") (pinfunction "1_1") (pintype "passive"))
      (node (ref "R39") (pin "1") (pinfunction "1_1") (pintype "passive"))
      (node (ref "R40") (pin "1") (pinfunction "1_1") (pintype "passive"))
      (node (ref "R41") (pin "1") (pinfunction "1_1") (pintype "passive"))
      (node (ref "R42") (pin "1") (pinfunction "1_1") (pintype "passive"))
      (node (ref "R43") (pin "1") (pinfunction "1_1") (pintype "passive"))
      (node (ref "R46") (pin "1") (pinfunction "1_1") (pintype "passive"))
      (node (ref "R47") (pin "1") (pinfunction "1_1") (pintype "passive"))
      (node (ref "R48") (pin "1") (pinfunction "1_1") (pintype "passive"))
      (node (ref "R50") (pin "1") (pinfunction "1_1") (pintype "passive"))
      (node (ref "R51") (pin "1") (pinfunction "1_1") (pintype "passive"))
      (node (ref "R52") (pin "1") (pinfunction "1_1") (pintype "passive"))
      (node (ref "R53") (pin "1") (pinfunction "1_1") (pintype "passive"))
      (node (ref "R54") (pin "1") (pinfunction "1_1") (pintype "passive"))
      (node (ref "U5") (pin "3") (pinfunction "VO_3") (pintype "passive"))
      (node (ref "U5") (pin "5") (pinfunction "VOSNS_5") (pintype "passive"))
    )
    (net (code "75") (name "GND") (class "Default")
      (node (ref "C102") (pin "2") (pinfunction "2_2") (pintype "passive"))
      (node (ref "C103") (pin "2") (pinfunction "2_2") (pintype "passive"))
      (node (ref "C104") (pin "2") (pinfunction "2_2") (pintype "passive"))
      (node (ref "C105") (pin "2") (pinfunction "2_2") (pintype "passive"))
      (node (ref "C106") (pin "2") (pinfunction "2_2") (pintype "passive"))
      (node (ref "C107") (pin "2") (pinfunction "2_2") (pintype "passive"))
      (node (ref "C108") (pin "2") (pinfunction "2_2") (pintype "passive"))
      (node (ref "C109") (pin "2") (pinfunction "2_2") (pintype "passive"))
      (node (ref "C110") (pin "2") (pinfunction "2_2") (pintype "passive"))
      (node (ref "C111") (pin "2") (pinfunction "2_2") (pintype "passive"))
      (node (ref "C112") (pin "2") (pinfunction "2_2") (pintype "passive"))
      (node (ref "C113") (pin "2") (pinfunction "2_2") (pintype "passive"))
      (node (ref "C114") (pin "2") (pinfunction "2_2") (pintype "passive"))
      (node (ref "C116") (pin "2") (pinfunction "2_2") (pintype "passive"))
      (node (ref "C117") (pin "2") (pinfunction "2_2") (pintype "passive"))
      (node (ref "C118") (pin "2") (pinfunction "2_2") (pintype "passive"))
      (node (ref "C119") (pin "2") (pinfunction "2_2") (pintype "passive"))
      (node (ref "C120") (pin "2") (pinfunction "2_2") (pintype "passive"))
      (node (ref "C121") (pin "2") (pinfunction "2_2") (pintype "passive"))
      (node (ref "C122") (pin "2") (pinfunction "2_2") (pintype "passive"))
      (node (ref "C123") (pin "2") (pinfunction "2_2") (pintype "passive"))
      (node (ref "C124") (pin "2") (pinfunction "2_2") (pintype "passive"))
      (node (ref "C125") (pin "2") (pinfunction "2_2") (pintype "passive"))
      (node (ref "C126") (pin "2") (pinfunction "2_2") (pintype "passive"))
      (node (ref "C127") (pin "2") (pinfunction "2_2") (pintype "passive"))
      (node (ref "C128") (pin "2") (pinfunction "2_2") (pintype "passive"))
      (node (ref "C129") (pin "2") (pinfunction "2_2") (pintype "passive"))
      (node (ref "C130") (pin "2") (pinfunction "2_2") (pintype "passive"))
      (node (ref "C131") (pin "2") (pinfunction "2_2") (pintype "passive"))
      (node (ref "C132") (pin "2") (pinfunction "2_2") (pintype "passive"))
      (node (ref "C133") (pin "2") (pinfunction "2_2") (pintype "passive"))
      (node (ref "C134") (pin "2") (pinfunction "2_2") (pintype "passive"))
      (node (ref "C135") (pin "2") (pinfunction "2_2") (pintype "passive"))
      (node (ref "C136") (pin "2") (pinfunction "2_2") (pintype "passive"))
      (node (ref "C137") (pin "2") (pinfunction "2_2") (pintype "passive"))
      (node (ref "C138") (pin "2") (pinfunction "2_2") (pintype "passive"))
      (node (ref "C139") (pin "2") (pinfunction "2_2") (pintype "passive"))
      (node (ref "C140") (pin "2") (pinfunction "2_2") (pintype "passive"))
      (node (ref "C141") (pin "2") (pinfunction "2_2") (pintype "passive"))
      (node (ref "C142") (pin "2") (pinfunction "2_2") (pintype "passive"))
      (node (ref "C143") (pin "2") (pinfunction "2_2") (pintype "passive"))
      (node (ref "C144") (pin "2") (pinfunction "2_2") (pintype "passive"))
      (node (ref "C145") (pin "2") (pinfunction "2_2") (pintype "passive"))
      (node (ref "C146") (pin "2") (pinfunction "2_2") (pintype "passive"))
      (node (ref "C147") (pin "2") (pinfunction "2_2") (pintype "passive"))
      (node (ref "C148") (pin "2") (pinfunction "2_2") (pintype "passive"))
      (node (ref "C149") (pin "2") (pinfunction "2_2") (pintype "passive"))
      (node (ref "C150") (pin "2") (pinfunction "2_2") (pintype "passive"))
      (node (ref "C229") (pin "2") (pinfunction "2_2") (pintype "passive"))
      (node (ref "C233") (pin "2") (pinfunction "2_2") (pintype "passive"))
      (node (ref "C234") (pin "2") (pinfunction "2_2") (pintype "passive"))
      (node (ref "C89") (pin "2") (pinfunction "2_2") (pintype "passive"))
      (node (ref "C90") (pin "2") (pinfunction "2_2") (pintype "passive"))
      (node (ref "C91") (pin "2") (pinfunction "2_2") (pintype "passive"))
      (node (ref "C92") (pin "2") (pinfunction "2_2") (pintype "passive"))
      (node (ref "C93") (pin "2") (pinfunction "2_2") (pintype "passive"))
      (node (ref "C94") (pin "2") (pinfunction "2_2") (pintype "passive"))
      (node (ref "C95") (pin "2") (pinfunction "2_2") (pintype "passive"))
      (node (ref "C96") (pin "2") (pinfunction "2_2") (pintype "passive"))
      (node (ref "C97") (pin "2") (pinfunction "2_2") (pintype "passive"))
      (node (ref "C98") (pin "2") (pinfunction "2_2") (pintype "passive"))
      (node (ref "C99") (pin "2") (pinfunction "2_2") (pintype "passive"))
      (node (ref "R105") (pin "1") (pinfunction "1_1") (pintype "passive"))
      (node (ref "R109") (pin "1") (pinfunction "1_1") (pintype "passive"))
      (node (ref "R44") (pin "1") (pinfunction "1_1") (pintype "passive"))
      (node (ref "R45") (pin "1") (pinfunction "1_1") (pintype "passive"))
      (node (ref "R49") (pin "2") (pinfunction "2_2") (pintype "passive"))
      (node (ref "R57") (pin "1") (pinfunction "1_1") (pintype "passive"))
      (node (ref "U3") (pin "A9") (pinfunction "VSS_A9") (pintype "power_in"))
      (node (ref "U3") (pin "B1") (pinfunction "VSSQ_B1") (pintype "power_in"))
      (node (ref "U3") (pin "B3") (pinfunction "VSS_B3") (pintype "power_in"))
      (node (ref "U3") (pin "B9") (pinfunction "VSSQ_B9") (pintype "power_in"))
      (node (ref "U3") (pin "D1") (pinfunction "VSSQ_D1") (pintype "power_in"))
      (node (ref "U3") (pin "D8") (pinfunction "VSSQ_D8") (pintype "power_in"))
      (node (ref "U3") (pin "E1") (pinfunction "VSS_E1") (pintype "power_in"))
      (node (ref "U3") (pin "E2") (pinfunction "VSSQ_E2") (pintype "power_in"))
      (node (ref "U3") (pin "E8") (pinfunction "VSSQ_E8") (pintype "power_in"))
      (node (ref "U3") (pin "F9") (pinfunction "VSSQ_F9") (pintype "power_in"))
      (node (ref "U3") (pin "G1") (pinfunction "VSSQ_G1") (pintype "power_in"))
      (node (ref "U3") (pin "G8") (pinfunction "VSS_G8") (pintype "power_in"))
      (node (ref "U3") (pin "G9") (pinfunction "VSSQ_G9") (pintype "power_in"))
      (node (ref "U3") (pin "J2") (pinfunction "VSS_J2") (pintype "power_in"))
      (node (ref "U3") (pin "J8") (pinfunction "VSS_J8") (pintype "power_in"))
      (node (ref "U3") (pin "M1") (pinfunction "VSS_M1") (pintype "power_in"))
      (node (ref "U3") (pin "M9") (pinfunction "VSS_M9") (pintype "power_in"))
      (node (ref "U3") (pin "P1") (pinfunction "VSS_P1") (pintype "power_in"))
      (node (ref "U3") (pin "P9") (pinfunction "VSS_P9") (pintype "power_in"))
      (node (ref "U3") (pin "T1") (pinfunction "VSS_T1") (pintype "power_in"))
      (node (ref "U3") (pin "T9") (pinfunction "VSS_T9") (pintype "power_in"))
      (node (ref "U4") (pin "A9") (pinfunction "VSS_A9") (pintype "power_in"))
      (node (ref "U4") (pin "B1") (pinfunction "VSSQ_B1") (pintype "power_in"))
      (node (ref "U4") (pin "B3") (pinfunction "VSS_B3") (pintype "power_in"))
      (node (ref "U4") (pin "B9") (pinfunction "VSSQ_B9") (pintype "power_in"))
      (node (ref "U4") (pin "D1") (pinfunction "VSSQ_D1") (pintype "power_in"))
      (node (ref "U4") (pin "D8") (pinfunction "VSSQ_D8") (pintype "power_in"))
      (node (ref "U4") (pin "E1") (pinfunction "VSS_E1") (pintype "power_in"))
      (node (ref "U4") (pin "E2") (pinfunction "VSSQ_E2") (pintype "power_in"))
      (node (ref "U4") (pin "E8") (pinfunction "VSSQ_E8") (pintype "power_in"))
      (node (ref "U4") (pin "F9") (pinfunction "VSSQ_F9") (pintype "power_in"))
      (node (ref "U4") (pin "G1") (pinfunction "VSSQ_G1") (pintype "power_in"))
      (node (ref "U4") (pin "G8") (pinfunction "VSS_G8") (pintype "power_in"))
      (node (ref "U4") (pin "G9") (pinfunction "VSSQ_G9") (pintype "power_in"))
      (node (ref "U4") (pin "J2") (pinfunction "VSS_J2") (pintype "power_in"))
      (node (ref "U4") (pin "J8") (pinfunction "VSS_J8") (pintype "power_in"))
      (node (ref "U4") (pin "M1") (pinfunction "VSS_M1") (pintype "power_in"))
      (node (ref "U4") (pin "M9") (pinfunction "VSS_M9") (pintype "power_in"))
      (node (ref "U4") (pin "P1") (pinfunction "VSS_P1") (pintype "power_in"))
      (node (ref "U4") (pin "P9") (pinfunction "VSS_P9") (pintype "power_in"))
      (node (ref "U4") (pin "T1") (pinfunction "VSS_T1") (pintype "power_in"))
      (node (ref "U4") (pin "T9") (pinfunction "VSS_T9") (pintype "power_in"))
      (node (ref "U5") (pin "11") (pinfunction "PWRGND_11") (pintype "passive"))
      (node (ref "U5") (pin "4") (pinfunction "PGND_4") (pintype "passive"))
      (node (ref "U5") (pin "8") (pinfunction "GND_8") (pintype "passive"))
    )
    (net (code "76") (name "Net-(U3-ZQ)") (class "Default")
      (node (ref "R45") (pin "2") (pinfunction "2_2") (pintype "passive"))
      (node (ref "U3") (pin "L8") (pinfunction "ZQ_L8") (pintype "power_in"))
    )
    (net (code "77") (name "Net-(U4-ZQ)") (class "Default")
      (node (ref "R44") (pin "2") (pinfunction "2_2") (pintype "passive"))
      (node (ref "U4") (pin "L8") (pinfunction "ZQ_L8") (pintype "power_in"))
    )
    (net (code "78") (name "Net-(U5-PGOOD)") (class "Default")
      (node (ref "R58") (pin "2") (pinfunction "2_2") (pintype "passive"))
      (node (ref "U5") (pin "9") (pinfunction "PGOOD_9") (pintype "passive"))
    )
    (net (code "79") (name "Net-(U5-REFIN)") (class "Default")
      (node (ref "C143") (pin "1") (pinfunction "1_1") (pintype "passive"))
      (node (ref "R56") (pin "1") (pinfunction "1_1") (pintype "passive"))
      (node (ref "R57") (pin "2") (pinfunction "2_2") (pintype "passive"))
      (node (ref "U5") (pin "1") (pinfunction "REFIN_1") (pintype "passive"))
    )
    (net (code "80") (name "VTTREF") (class "Default")
      (node (ref "C100") (pin "2") (pinfunction "2_2") (pintype "passive"))
      (node (ref "C101") (pin "2") (pinfunction "2_2") (pintype "passive"))
      (node (ref "C102") (pin "1") (pinfunction "1_1") (pintype "passive"))
      (node (ref "C103") (pin "1") (pinfunction "1_1") (pintype "passive"))
      (node (ref "C149") (pin "1") (pinfunction "1_1") (pintype "passive"))
      (node (ref "C150") (pin "1") (pinfunction "1_1") (pintype "passive"))
      (node (ref "C229") (pin "1") (pinfunction "1_1") (pintype "passive"))
      (node (ref "C230") (pin "2") (pinfunction "2_2") (pintype "passive"))
      (node (ref "R104") (pin "1") (pinfunction "1_1") (pintype "passive"))
      (node (ref "R105") (pin "2") (pinfunction "2_2") (pintype "passive"))
      (node (ref "U3") (pin "H1") (pinfunction "VREFDQ_H1") (pintype "power_in"))
      (node (ref "U3") (pin "M8") (pinfunction "VREFCA_M8") (pintype "power_in"))
      (node (ref "U4") (pin "H1") (pinfunction "VREFDQ_H1") (pintype "power_in"))
      (node (ref "U4") (pin "M8") (pinfunction "VREFCA_M8") (pintype "power_in"))
      (node (ref "U5") (pin "6") (pinfunction "REFOUT_6") (pintype "passive"))
    )
    (net (code "81") (name "unconnected-(U3-NC1-PadJ1)") (class "Default")
      (node (ref "U3") (pin "J1") (pinfunction "NC1_J1") (pintype "passive+no_connect"))
    )
    (net (code "82") (name "unconnected-(U3-NC2-PadJ9)") (class "Default")
      (node (ref "U3") (pin "J9") (pinfunction "NC2_J9") (pintype "passive+no_connect"))
    )
    (net (code "83") (name "unconnected-(U3-NC3-PadL1)") (class "Default")
      (node (ref "U3") (pin "L1") (pinfunction "NC3_L1") (pintype "passive+no_connect"))
    )
    (net (code "84") (name "unconnected-(U3-NC4-PadL9)") (class "Default")
      (node (ref "U3") (pin "L9") (pinfunction "NC4_L9") (pintype "passive+no_connect"))
    )
    (net (code "85") (name "unconnected-(U3-NC5-PadM7)") (class "Default")
      (node (ref "U3") (pin "M7") (pinfunction "NC5_M7") (pintype "passive+no_connect"))
    )
    (net (code "86") (name "unconnected-(U4-NC1-PadJ1)") (class "Default")
      (node (ref "U4") (pin "J1") (pinfunction "NC1_J1") (pintype "passive+no_connect"))
    )
    (net (code "87") (name "unconnected-(U4-NC2-PadJ9)") (class "Default")
      (node (ref "U4") (pin "J9") (pinfunction "NC2_J9") (pintype "passive+no_connect"))
    )
    (net (code "88") (name "unconnected-(U4-NC3-PadL1)") (class "Default")
      (node (ref "U4") (pin "L1") (pinfunction "NC3_L1") (pintype "passive+no_connect"))
    )
    (net (code "89") (name "unconnected-(U4-NC4-PadL9)") (class "Default")
      (node (ref "U4") (pin "L9") (pinfunction "NC4_L9") (pintype "passive+no_connect"))
    )
    (net (code "90") (name "unconnected-(U4-NC5-PadM7)") (class "Default")
      (node (ref "U4") (pin "M7") (pinfunction "NC5_M7") (pintype "passive+no_connect"))
    )
  )
)
